# Conduino-V01.net
KiCad netlist of a schematic drawn in EAGLE
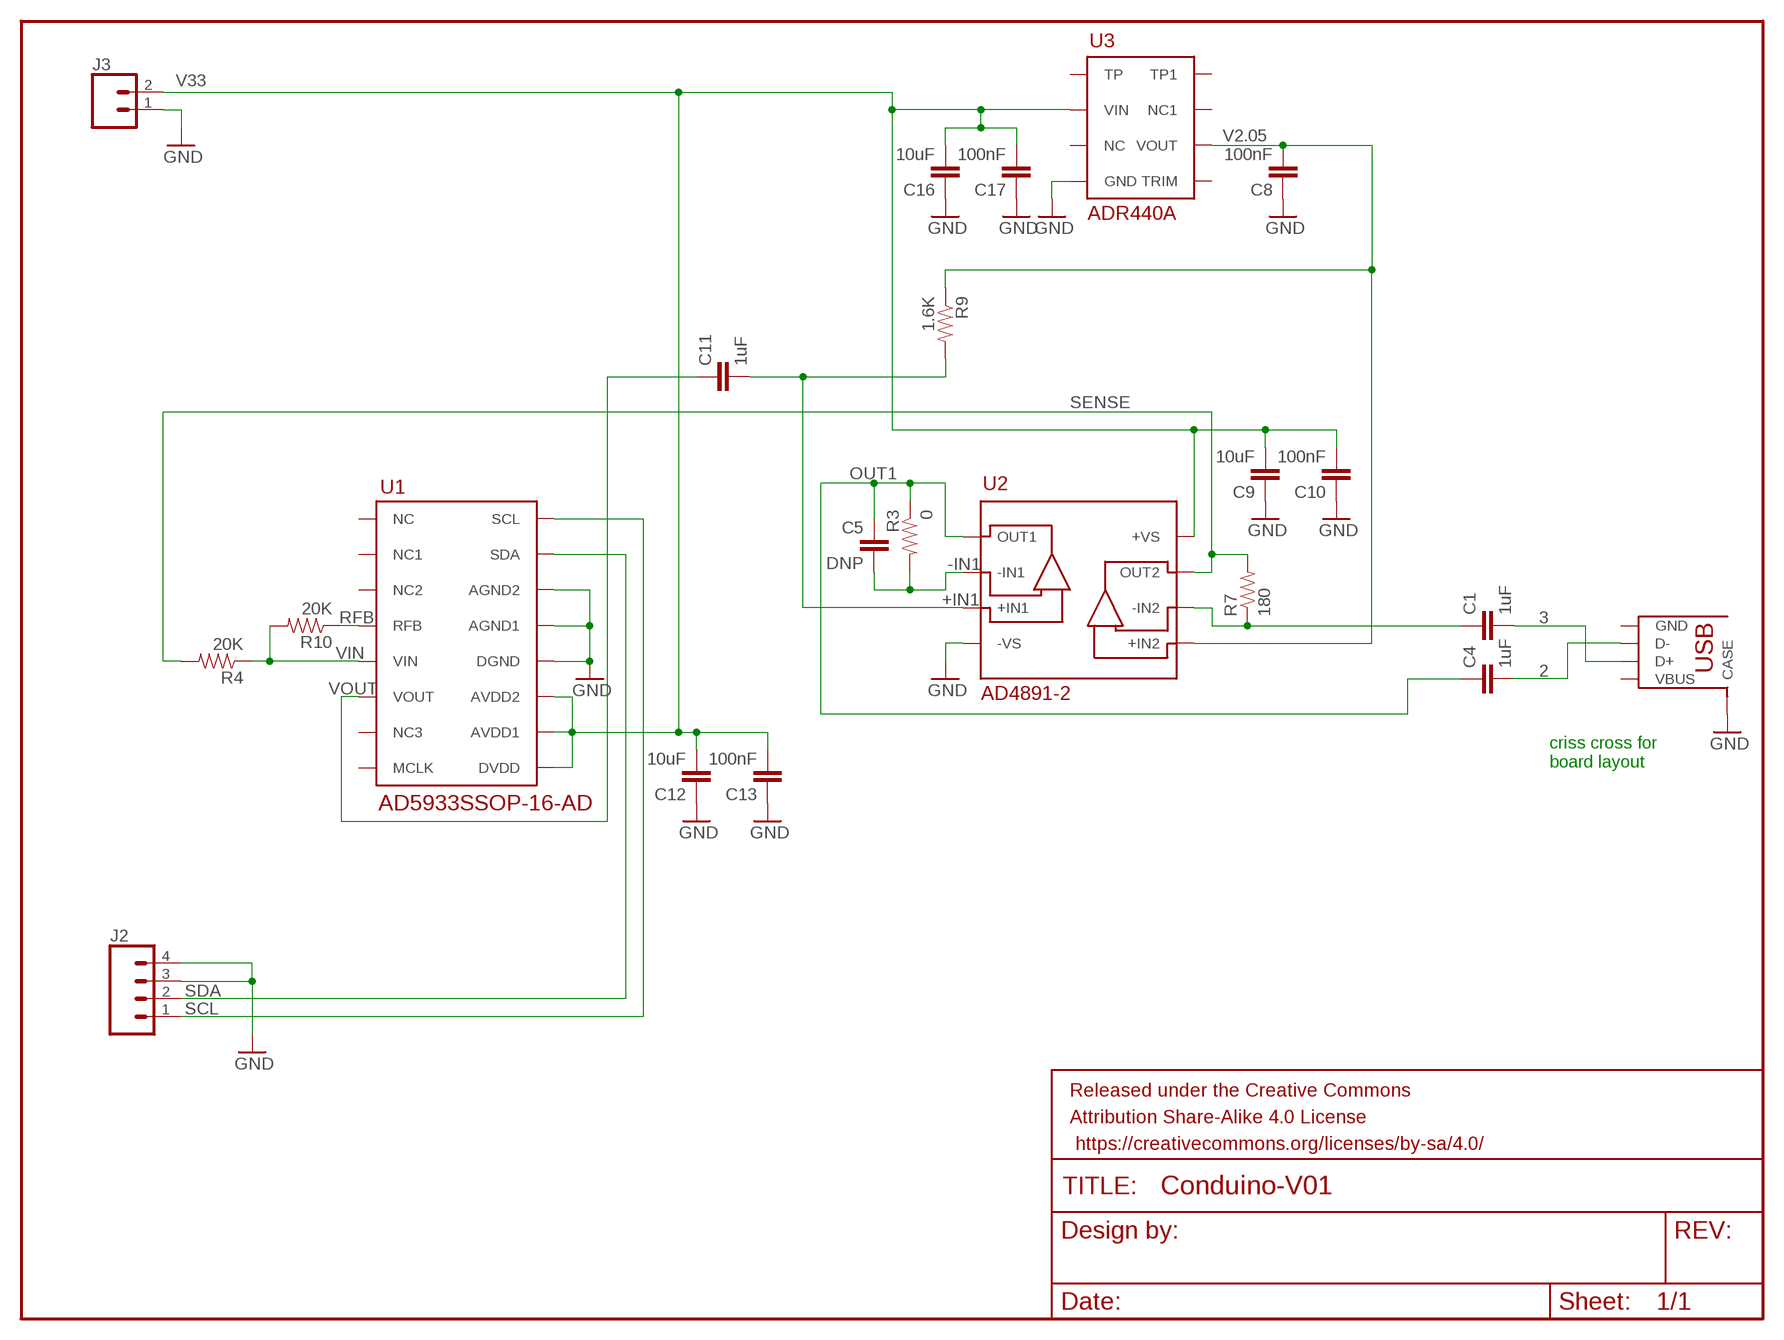
[diagram p0: schematic, sheet 1]

(export (version "E")
  (design (tool "Eeschema 10.0.6"))
  (components
    (comp (ref "C1")
      (value "1uF")
      (footprint "eagle-import:0603-CAP")
      (libsource (lib "eagle-import") (part "CAP0603-CAP"))
    )
    (comp (ref "C4")
      (value "1uF")
      (footprint "eagle-import:0603-CAP")
      (libsource (lib "eagle-import") (part "CAP0603-CAP"))
    )
    (comp (ref "C5")
      (value "DNP")
      (footprint "eagle-import:0603-CAP")
      (libsource (lib "eagle-import") (part "CAP0603-CAP"))
    )
    (comp (ref "C8")
      (value "100nF")
      (footprint "eagle-import:0603-CAP")
      (libsource (lib "eagle-import") (part "CAP0603-CAP"))
    )
    (comp (ref "C9")
      (value "10uF")
      (footprint "eagle-import:0603-CAP")
      (libsource (lib "eagle-import") (part "CAP0603-CAP"))
    )
    (comp (ref "C10")
      (value "100nF")
      (footprint "eagle-import:0603-CAP")
      (libsource (lib "eagle-import") (part "CAP0603-CAP"))
    )
    (comp (ref "C11")
      (value "1uF")
      (footprint "eagle-import:0603-CAP")
      (libsource (lib "eagle-import") (part "CAP0603-CAP"))
    )
    (comp (ref "C12")
      (value "10uF")
      (footprint "eagle-import:0603-CAP")
      (libsource (lib "eagle-import") (part "CAP0603-CAP"))
    )
    (comp (ref "C13")
      (value "100nF")
      (footprint "eagle-import:0603-CAP")
      (libsource (lib "eagle-import") (part "CAP0603-CAP"))
    )
    (comp (ref "C16")
      (value "10uF")
      (footprint "eagle-import:0603-CAP")
      (libsource (lib "eagle-import") (part "CAP0603-CAP"))
    )
    (comp (ref "C17")
      (value "100nF")
      (footprint "eagle-import:0603-CAP")
      (libsource (lib "eagle-import") (part "CAP0603-CAP"))
    )
    (comp (ref "FRAME1")
      (value "FRAME-LETTER")
      (footprint "eagle-import:CREATIVE_COMMONS")
      (libsource (lib "eagle-import") (part "FRAME-LETTER"))
    )
    (comp (ref "J1")
      (value "USBA-SIDE")
      (footprint "eagle-import:USBA-SIDE")
      (libsource (lib "eagle-import") (part "USBA-SIDE"))
    )
    (comp (ref "J2")
      (value "CONN_041X04_NO_SILK")
      (footprint "eagle-import:1X04_NO_SILK")
      (libsource (lib "eagle-import") (part "CONN_041X04_NO_SILK"))
    )
    (comp (ref "J3")
      (value "CONN_021X02_NO_SILK")
      (footprint "eagle-import:1X02_NO_SILK")
      (libsource (lib "eagle-import") (part "CONN_021X02_NO_SILK"))
    )
    (comp (ref "R3")
      (value "0")
      (footprint "eagle-import:0603-RES")
      (libsource (lib "eagle-import") (part "RESISTOR0603-RES"))
    )
    (comp (ref "R4")
      (value "20K")
      (footprint "eagle-import:0603-RES")
      (libsource (lib "eagle-import") (part "RESISTOR0603-RES"))
    )
    (comp (ref "R7")
      (value "180")
      (footprint "eagle-import:0603-RES")
      (libsource (lib "eagle-import") (part "RESISTOR0603-RES"))
    )
    (comp (ref "R9")
      (value "1.6K")
      (footprint "eagle-import:0603-RES")
      (libsource (lib "eagle-import") (part "RESISTOR0603-RES"))
    )
    (comp (ref "R10")
      (value "20K")
      (footprint "eagle-import:0603-RES")
      (libsource (lib "eagle-import") (part "RESISTOR0603-RES"))
    )
    (comp (ref "U1")
      (value "AD5933SSOP-16-AD")
      (footprint "eagle-import:SSOP-16-AD")
      (libsource (lib "eagle-import") (part "AD5933SSOP-16-AD"))
    )
    (comp (ref "U2")
      (value "AD4891-2")
      (footprint "eagle-import:SOIC_N")
      (libsource (lib "eagle-import") (part "AD4891-2"))
    )
    (comp (ref "U3")
      (value "ADR440A")
      (footprint "eagle-import:SOIC_N")
      (libsource (lib "eagle-import") (part "ADR440A"))
    )
  )
  (nets
    (net (code "1") (name "/+IN1") (class "Default")
      (node (ref "C11") (pin "2") (pinfunction "2_2") (pintype "passive"))
      (node (ref "R9") (pin "2") (pinfunction "2_2") (pintype "passive"))
      (node (ref "U2") (pin "P$3") (pinfunction "+IN1_P$3") (pintype "bidirectional"))
    )
    (net (code "2") (name "/-IN1") (class "Default")
      (node (ref "C5") (pin "2") (pinfunction "2_2") (pintype "passive"))
      (node (ref "R3") (pin "2") (pinfunction "2_2") (pintype "passive"))
      (node (ref "U2") (pin "P$2") (pinfunction "-IN1_P$2") (pintype "bidirectional"))
    )
    (net (code "3") (name "/2") (class "Default")
      (node (ref "C4") (pin "2") (pinfunction "2_2") (pintype "passive"))
      (node (ref "J1") (pin "P$2") (pinfunction "D-_P$2") (pintype "bidirectional"))
    )
    (net (code "4") (name "/3") (class "Default")
      (node (ref "C1") (pin "2") (pinfunction "2_2") (pintype "passive"))
      (node (ref "J1") (pin "P$3") (pinfunction "D+_P$3") (pintype "bidirectional"))
    )
    (net (code "5") (name "/OUT1") (class "Default")
      (node (ref "C4") (pin "1") (pinfunction "1_1") (pintype "passive"))
      (node (ref "C5") (pin "1") (pinfunction "1_1") (pintype "passive"))
      (node (ref "R3") (pin "1") (pinfunction "1_1") (pintype "passive"))
      (node (ref "U2") (pin "P$1") (pinfunction "OUT1_P$1") (pintype "bidirectional"))
    )
    (net (code "6") (name "/RFB") (class "Default")
      (node (ref "R10") (pin "1") (pinfunction "1_1") (pintype "passive"))
      (node (ref "U1") (pin "P$4") (pinfunction "RFB_P$4") (pintype "passive"))
    )
    (net (code "7") (name "/SCL") (class "Default")
      (node (ref "J2") (pin "1") (pinfunction "1_1") (pintype "passive"))
      (node (ref "U1") (pin "P$16") (pinfunction "SCL_P$16") (pintype "passive"))
    )
    (net (code "8") (name "/SDA") (class "Default")
      (node (ref "J2") (pin "2") (pinfunction "2_2") (pintype "passive"))
      (node (ref "U1") (pin "P$15") (pinfunction "SDA_P$15") (pintype "passive"))
    )
    (net (code "9") (name "/SENSE") (class "Default")
      (node (ref "R4") (pin "2") (pinfunction "2_2") (pintype "passive"))
      (node (ref "R7") (pin "2") (pinfunction "2_2") (pintype "passive"))
      (node (ref "U2") (pin "P$7") (pinfunction "OUT2_P$7") (pintype "bidirectional"))
    )
    (net (code "10") (name "/V2.05") (class "Default")
      (node (ref "C8") (pin "2") (pinfunction "2_2") (pintype "passive"))
      (node (ref "R9") (pin "1") (pinfunction "1_1") (pintype "passive"))
      (node (ref "U2") (pin "P$5") (pinfunction "+IN2_P$5") (pintype "bidirectional"))
      (node (ref "U3") (pin "P$6") (pinfunction "VOUT_P$6") (pintype "bidirectional"))
    )
    (net (code "11") (name "/V33") (class "Default")
      (node (ref "C10") (pin "2") (pinfunction "2_2") (pintype "passive"))
      (node (ref "C12") (pin "2") (pinfunction "2_2") (pintype "passive"))
      (node (ref "C13") (pin "2") (pinfunction "2_2") (pintype "passive"))
      (node (ref "C16") (pin "2") (pinfunction "2_2") (pintype "passive"))
      (node (ref "C17") (pin "2") (pinfunction "2_2") (pintype "passive"))
      (node (ref "C9") (pin "2") (pinfunction "2_2") (pintype "passive"))
      (node (ref "J3") (pin "2") (pinfunction "2_2") (pintype "passive"))
      (node (ref "U1") (pin "P$10") (pinfunction "AVDD1_P$10") (pintype "passive"))
      (node (ref "U1") (pin "P$11") (pinfunction "AVDD2_P$11") (pintype "passive"))
      (node (ref "U1") (pin "P$9") (pinfunction "DVDD_P$9") (pintype "passive"))
      (node (ref "U2") (pin "P$8") (pinfunction "+VS_P$8") (pintype "bidirectional"))
      (node (ref "U3") (pin "P$2") (pinfunction "VIN_P$2") (pintype "bidirectional"))
    )
    (net (code "12") (name "/VIN") (class "Default")
      (node (ref "R10") (pin "2") (pinfunction "2_2") (pintype "passive"))
      (node (ref "R4") (pin "1") (pinfunction "1_1") (pintype "passive"))
      (node (ref "U1") (pin "P$5") (pinfunction "VIN_P$5") (pintype "passive"))
    )
    (net (code "13") (name "/VOUT") (class "Default")
      (node (ref "C11") (pin "1") (pinfunction "1_1") (pintype "passive"))
      (node (ref "U1") (pin "P$6") (pinfunction "VOUT_P$6") (pintype "passive"))
    )
    (net (code "14") (name "GND") (class "Default")
      (node (ref "C10") (pin "1") (pinfunction "1_1") (pintype "passive"))
      (node (ref "C12") (pin "1") (pinfunction "1_1") (pintype "passive"))
      (node (ref "C13") (pin "1") (pinfunction "1_1") (pintype "passive"))
      (node (ref "C16") (pin "1") (pinfunction "1_1") (pintype "passive"))
      (node (ref "C17") (pin "1") (pinfunction "1_1") (pintype "passive"))
      (node (ref "C8") (pin "1") (pinfunction "1_1") (pintype "passive"))
      (node (ref "C9") (pin "1") (pinfunction "1_1") (pintype "passive"))
      (node (ref "J1") (pin "P$5") (pinfunction "CASE_P$5") (pintype "bidirectional"))
      (node (ref "J1") (pin "P$6") (pinfunction "CASE_P$6") (pintype "bidirectional"))
      (node (ref "J2") (pin "3") (pinfunction "3_3") (pintype "passive"))
      (node (ref "J2") (pin "4") (pinfunction "4_4") (pintype "passive"))
      (node (ref "J3") (pin "1") (pinfunction "1_1") (pintype "passive"))
      (node (ref "U1") (pin "P$12") (pinfunction "DGND_P$12") (pintype "passive"))
      (node (ref "U1") (pin "P$13") (pinfunction "AGND1_P$13") (pintype "passive"))
      (node (ref "U1") (pin "P$14") (pinfunction "AGND2_P$14") (pintype "passive"))
      (node (ref "U2") (pin "P$4") (pinfunction "-VS_P$4") (pintype "bidirectional"))
      (node (ref "U3") (pin "P$4") (pinfunction "GND_P$4") (pintype "bidirectional"))
    )
    (net (code "15") (name "Net-(U2--IN2)") (class "Default")
      (node (ref "C1") (pin "1") (pinfunction "1_1") (pintype "passive"))
      (node (ref "R7") (pin "1") (pinfunction "1_1") (pintype "passive"))
      (node (ref "U2") (pin "P$6") (pinfunction "-IN2_P$6") (pintype "bidirectional"))
    )
    (net (code "16") (name "unconnected-(J1-GND-PadP$1)") (class "Default")
      (node (ref "J1") (pin "P$1") (pinfunction "GND_P$1") (pintype "bidirectional"))
    )
    (net (code "17") (name "unconnected-(J1-VBUS-PadP$4)") (class "Default")
      (node (ref "J1") (pin "P$4") (pinfunction "VBUS_P$4") (pintype "bidirectional"))
    )
    (net (code "18") (name "unconnected-(U1-MCLK-PadP$8)") (class "Default")
      (node (ref "U1") (pin "P$8") (pinfunction "MCLK_P$8") (pintype "passive"))
    )
    (net (code "19") (name "unconnected-(U1-NC-PadP$1)") (class "Default")
      (node (ref "U1") (pin "P$1") (pinfunction "NC_P$1") (pintype "passive"))
    )
    (net (code "20") (name "unconnected-(U1-NC1-PadP$2)") (class "Default")
      (node (ref "U1") (pin "P$2") (pinfunction "NC1_P$2") (pintype "passive"))
    )
    (net (code "21") (name "unconnected-(U1-NC2-PadP$3)") (class "Default")
      (node (ref "U1") (pin "P$3") (pinfunction "NC2_P$3") (pintype "passive"))
    )
    (net (code "22") (name "unconnected-(U1-NC3-PadP$7)") (class "Default")
      (node (ref "U1") (pin "P$7") (pinfunction "NC3_P$7") (pintype "passive"))
    )
    (net (code "23") (name "unconnected-(U3-NC-PadP$3)") (class "Default")
      (node (ref "U3") (pin "P$3") (pinfunction "NC_P$3") (pintype "bidirectional"))
    )
    (net (code "24") (name "unconnected-(U3-NC1-PadP$7)") (class "Default")
      (node (ref "U3") (pin "P$7") (pinfunction "NC1_P$7") (pintype "bidirectional"))
    )
    (net (code "25") (name "unconnected-(U3-TP-PadP$1)") (class "Default")
      (node (ref "U3") (pin "P$1") (pinfunction "TP_P$1") (pintype "bidirectional"))
    )
    (net (code "26") (name "unconnected-(U3-TP1-PadP$8)") (class "Default")
      (node (ref "U3") (pin "P$8") (pinfunction "TP1_P$8") (pintype "bidirectional"))
    )
    (net (code "27") (name "unconnected-(U3-TRIM-PadP$5)") (class "Default")
      (node (ref "U3") (pin "P$5") (pinfunction "TRIM_P$5") (pintype "bidirectional"))
    )
  )
)
